# Sensor_LoRa_Moist.net
KiCad netlist of a schematic drawn in Altium Designer
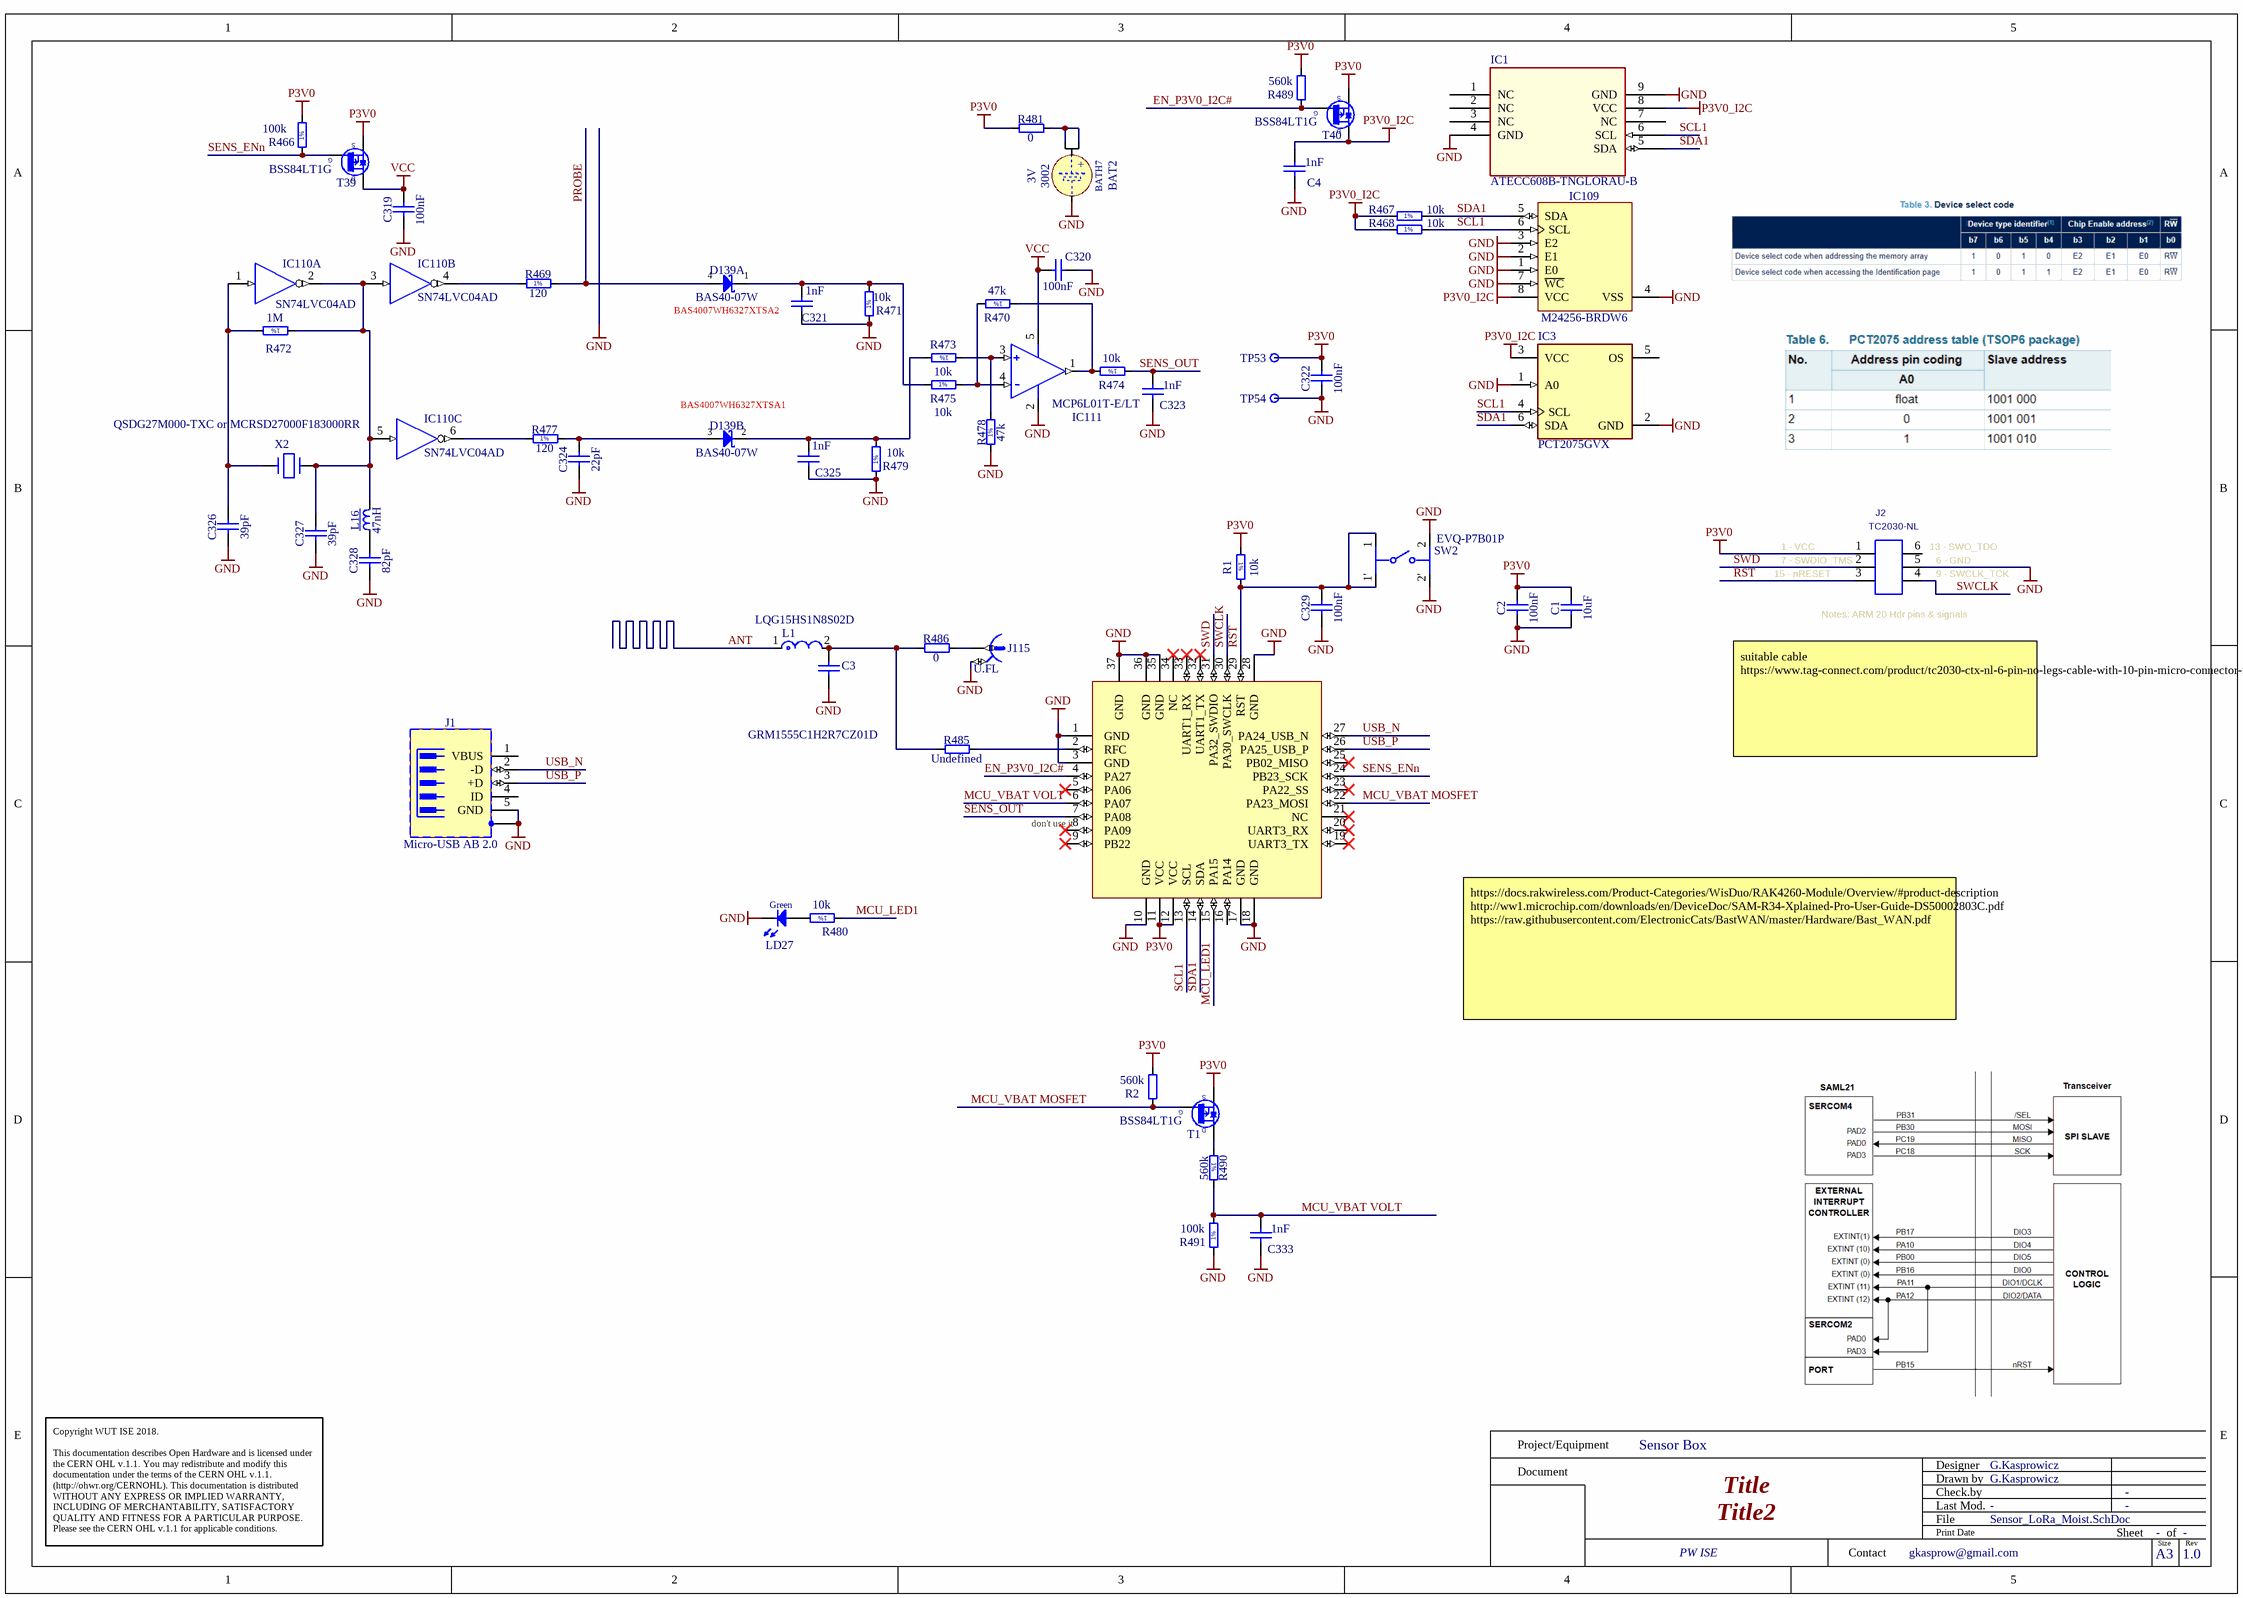
[diagram p0: Sensor_LoRa_Moist.SchDoc]

(export (version "E")
  (design (tool "Eeschema 10.0.6"))
  (components
    (comp (ref "BAT2")
      (value "3V")
      (footprint "BAT_VARTA_CR2032")
      (description "Battery for use only with Socket Holder")
      (fields
        (field (name "PART NUMBER") "BAT_VARTA_CR2032")
        (field (name "POWER") "230mAh")
        (field (name "AUTHOR") "CERN DEM JLC")
      )
      (libsource (lib "Eletro-mechanical") (part "Battery No Pin"))
    )
    (comp (ref "BATH7")
      (value "3002")
      (footprint "KEYSTONE 3002")
      (description "Battery Holder Keystone 3002")
      (fields
        (field (name "PART NUMBER") "BATH_KEYSTONE_3000")
        (field (name "MANUFACTURER") "KEYSTONE")
        (field (name "AUTHOR") "GK")
      )
      (libsource (lib "LIBRARY_SCH") (part "BATTERY_HOLD_CR2032_SMD"))
    )
    (comp (ref "C1")
      (value "10uF")
      (footprint "CAPC2012X135N")
      (description "Non-polarised capacitor")
      (fields
        (field (name "PART NUMBER") "CC0805_10UF_16V_10%_X5R")
        (field (name "VOLTAGE") "16V")
        (field (name "AUTHOR") "CERN DEM JLC")
      )
      (libsource (lib "Capacitors") (part "Capacitor - non polarized"))
    )
    (comp (ref "C2")
      (value "100nF")
      (footprint "CAPC1005X55N")
      (description "Non-polarised capacitor")
      (fields
        (field (name "PART NUMBER") "CC0402_100NF_16V_10%_X5R")
        (field (name "VOLTAGE") "16V")
        (field (name "AUTHOR") "CERN DEM JLC")
      )
      (libsource (lib "Capacitors") (part "Capacitor - non polarized"))
    )
    (comp (ref "C3")
      (value "GRM1555C1H2R7CZ01D")
      (footprint "CAPC1005X55X25ML05T10")
      (fields (field (name "MANUFACTURER") "Murata"))
      (libsource (lib "Altium Content Vault") (part "CAP"))
    )
    (comp (ref "C4")
      (value "1nF")
      (footprint "CAPC1005X55N")
      (description "Non-polarised capacitor")
      (fields
        (field (name "PART NUMBER") "CC0402_1NF_50V_10%_X7R")
        (field (name "VOLTAGE") "50V")
        (field (name "AUTHOR") "CERN DEM JLC")
      )
      (libsource (lib "Capacitors") (part "Capacitor - non polarized"))
    )
    (comp (ref "C319")
      (value "100nF")
      (footprint "CAPC1005X55N")
      (description "Non-polarised capacitor")
      (fields
        (field (name "PART NUMBER") "CC0402_100NF_16V_10%_X5R")
        (field (name "VOLTAGE") "16V")
        (field (name "AUTHOR") "CERN DEM JLC")
      )
      (libsource (lib "Capacitors") (part "Capacitor - non polarized"))
    )
    (comp (ref "C320")
      (value "100nF")
      (footprint "CAPC1005X55N")
      (description "Non-polarised capacitor")
      (fields
        (field (name "PART NUMBER") "CC0402_100NF_16V_10%_X5R")
        (field (name "VOLTAGE") "16V")
        (field (name "AUTHOR") "CERN DEM JLC")
      )
      (libsource (lib "Capacitors") (part "Capacitor - non polarized"))
    )
    (comp (ref "C321")
      (value "1nF")
      (footprint "CAPC1005X55N")
      (description "Non-polarised capacitor")
      (fields
        (field (name "PART NUMBER") "CC0402_1NF_50V_10%_X7R")
        (field (name "VOLTAGE") "50V")
        (field (name "AUTHOR") "CERN DEM JLC")
      )
      (libsource (lib "Capacitors") (part "Capacitor - non polarized"))
    )
    (comp (ref "C322")
      (value "100nF")
      (footprint "CAPC1005X55N")
      (description "Non-polarised capacitor")
      (fields
        (field (name "PART NUMBER") "CC0402_100NF_16V_10%_X5R")
        (field (name "VOLTAGE") "16V")
        (field (name "AUTHOR") "CERN DEM JLC")
      )
      (libsource (lib "Capacitors") (part "Capacitor - non polarized"))
    )
    (comp (ref "C323")
      (value "1nF")
      (footprint "CAPC1005X55N")
      (description "Non-polarised capacitor")
      (fields
        (field (name "PART NUMBER") "CC0402_1NF_50V_10%_X7R")
        (field (name "VOLTAGE") "50V")
        (field (name "AUTHOR") "CERN DEM JLC")
      )
      (libsource (lib "Capacitors") (part "Capacitor - non polarized"))
    )
    (comp (ref "C324")
      (value "22pF")
      (footprint "CAPC1005X55N")
      (description "Non-polarised capacitor")
      (fields
        (field (name "PART NUMBER") "CC0402_22PF_50V_5%_C0G")
        (field (name "VOLTAGE") "50V")
        (field (name "AUTHOR") "CERN DEM JLC")
      )
      (libsource (lib "Capacitors") (part "Capacitor - non polarized"))
    )
    (comp (ref "C325")
      (value "1nF")
      (footprint "CAPC1005X55N")
      (description "Non-polarised capacitor")
      (fields
        (field (name "PART NUMBER") "CC0402_1NF_50V_10%_X7R")
        (field (name "VOLTAGE") "50V")
        (field (name "AUTHOR") "CERN DEM JLC")
      )
      (libsource (lib "Capacitors") (part "Capacitor - non polarized"))
    )
    (comp (ref "C326")
      (value "39pF")
      (footprint "CAPC1608X87N")
      (description "Non-polarised capacitor")
      (fields
        (field (name "PART NUMBER") "CC0603_39PF_50V_5%_NP0")
        (field (name "VOLTAGE") "50V")
        (field (name "AUTHOR") "CERN DEM JLC")
      )
      (libsource (lib "Capacitors") (part "Capacitor - non polarized"))
    )
    (comp (ref "C327")
      (value "39pF")
      (footprint "CAPC1608X87N")
      (description "Non-polarised capacitor")
      (fields
        (field (name "PART NUMBER") "CC0603_39PF_50V_5%_NP0")
        (field (name "VOLTAGE") "50V")
        (field (name "AUTHOR") "CERN DEM JLC")
      )
      (libsource (lib "Capacitors") (part "Capacitor - non polarized"))
    )
    (comp (ref "C328")
      (value "82pF")
      (footprint "CAPC2012X90N")
      (description "Non-polarised capacitor")
      (fields
        (field (name "PART NUMBER") "CC0805_82PF_100V_1%_NP0_AVX_08051A820FAT2A")
        (field (name "VOLTAGE") "100V")
        (field (name "AUTHOR") "CERN DEM WB")
      )
      (libsource (lib "Capacitors") (part "Capacitor - non polarized"))
    )
    (comp (ref "C329")
      (value "100nF")
      (footprint "CAPC1005X55N")
      (description "Non-polarised capacitor")
      (fields
        (field (name "PART NUMBER") "CC0402_100NF_16V_10%_X5R")
        (field (name "VOLTAGE") "16V")
        (field (name "AUTHOR") "CERN DEM JLC")
      )
      (libsource (lib "Capacitors") (part "Capacitor - non polarized"))
    )
    (comp (ref "C333")
      (value "1nF")
      (footprint "CAPC1005X55N")
      (description "Non-polarised capacitor")
      (fields
        (field (name "PART NUMBER") "CC0402_1NF_50V_10%_X7R")
        (field (name "VOLTAGE") "50V")
        (field (name "AUTHOR") "CERN DEM JLC")
      )
      (libsource (lib "Capacitors") (part "Capacitor - non polarized"))
    )
    (comp (ref "D139")
      (value "BAS40-07W")
      (footprint "INFINEON-PG-SOT343-4")
      (description "Anti-Parallel Pair Schottky Diode")
      (fields
        (field (name "PART NUMBER") "BAS4007WH6327XTSA1")
        (field (name "VOLTAGE") "4V")
        (field (name "AUTHOR") "GK")
      )
      (libsource (lib "LIBRARY_SCH") (part "D_BAS40-07W"))
    )
    (comp (ref "IC1")
      (value "ATECC608B-TNGLORAU-B")
      (footprint "UDFN8_MUY/Q4B_MCH-L")
      (description "Pre-provisioned secure element for LoRaWAN")
      (fields (field (name "COPYRIGHT") "Copyright (C) 2018 Accelerated Designs. All rights reserved"))
      (libsource (lib "ICs_Analog_Interfaces") (part "CRYPTO_ATECC608B-TNGLORAU-B"))
    )
    (comp (ref "IC2")
      (value "RAK4260 - EU868")
      (footprint "RAK4260")
      (description "RAK4260 LoRaWAN module from RAKwireless.")
      (fields (field (name "MANUFACTURER") "RAK WIreless"))
      (libsource (lib "Modules") (part "RF_RAK4260"))
    )
    (comp (ref "IC3")
      (value "PCT2075GVX")
      (footprint "FP-SOT1353-1-MFG")
      (description "SENSOR DIGITAL -55C-125C 6TSOP")
      (fields
        (field (name "MANUFACTURER") "NXP Semiconductors")
        (field (name "OCTOPART") "https://octopart.com/pct2075gvx-nxp+semiconductors-50417606")
      )
      (libsource (lib "Altium Content Vault") (part "9e3f1a7ca589d645a6d0162f869e50e"))
    )
    (comp (ref "IC109")
      (value "M24256-BRDW6")
      (footprint "SOP65P640X120-8N")
      (description "256-Kbit Serial I²C Bus EEPROM")
      (fields
        (field (name "PART NUMBER") "M24256-BRDW6P")
        (field (name "MANUFACTURER") "ST MICROELECTRONICS")
        (field (name "AUTHOR") "CERN DEM MR")
      )
      (libsource (lib "LIBRARY_SCH") (part "MEM_M24256-BRDW6P"))
    )
    (comp (ref "IC110")
      (value "SN74LVC04AD")
      (footprint "SOIC127P600X175-14N")
      (description "Hex Inverter")
      (fields (field (name "MANUFACTURER") "TEXAS INSTRUMENTS") (field (name "AUTHOR") "CERN DEM JLC"))
      (libsource (lib "ICs And Semiconductors") (part "7404"))
    )
    (comp (ref "IC111")
      (value "MCP6L01T-E/LT")
      (footprint "SC70")
      (description "1 MHz, Low-Power Op Amp")
      (libsource (lib "LIBRARY_SCH") (part "OA_MCP6001_SC-70"))
    )
    (comp (ref "J1")
      (value "Micro-USB AB 2.0")
      (footprint "HIROSE_ZX62RD-AB-5P8")
      (description "5 Pin + 1 Shield USB Receptacle")
      (fields
        (field (name "PART NUMBER") "HIROSE_ZX62RD-AB-5P8")
        (field (name "MANUFACTURER") "HIROSE (HRS)")
        (field (name "AUTHOR") "CERN DEM JLC")
      )
      (libsource (lib "Connectors") (part "Connector USB 5 Pin + 1Shield"))
    )
    (comp (ref "J2")
      (value "TC2030-NL")
      (footprint "TC2030-IDC")
      (description "HDR, TC2030, 6 Pin, Footprint only")
      (libsource (lib "TagConnect-20Apr2013") (part "HDR 6 TC2030-NL"))
    )
    (comp (ref "J115")
      (value "U.FL")
      (footprint "HIROSE_U.FL-R-SMT-1(10)")
      (fields
        (field (name "PART NUMBER") "HIROSE_U.FL-R-SMT-1(10)")
        (field (name "MANUFACTURER") "HIROSE (HRS)")
        (field (name "MANUFACTURER PART NUMBER") "U.FL-R-SMT-1(10)")
        (field (name "AUTHOR") "CERN DEM JLC")
      )
      (libsource (lib "Connectors") (part "Coax_1Male_1Shield"))
    )
    (comp (ref "L1")
      (value "LQG15HS1N8S02D")
      (footprint "FP-LQG15HH_02-IPC_C")
      (description "Multilayer type RF Inductor 1.8nH ±0.3nH 0.08Ω 950mA 0402")
      (libsource (lib "Altium Content Vault") (part "4cc4b267dca4c8e51f7102f422741d8"))
    )
    (comp (ref "L16")
      (value "47nH")
      (footprint "IND_COILCRAFT_0805CS")
      (description "Inductor With Core")
      (fields
        (field (name "PART NUMBER") "IND_47NH_2%_COILCRAFT_0805CS")
        (field (name "POWER") "500mA")
        (field (name "AUTHOR") "CERN DEM JLC")
      )
      (libsource (lib "Inductors & Transformers") (part "Inductor With Magnetic core"))
    )
    (comp (ref "LD27")
      (value "Green")
      (footprint "LED_KINGBRIGHT_KPH-1608CGCK")
      (description "LED Green 1C 2A")
      (fields
        (field (name "PART NUMBER") "LED_KINGBRIGHT_KPH-1608CGCK")
        (field (name "MANUFACTURER") "KINGBRIGHT")
        (field (name "AUTHOR") "CERN DEM JLC")
      )
      (libsource (lib "ICs And Semiconductors") (part "LED Green 1C 2A"))
    )
    (comp (ref "R1")
      (value "10k")
      (footprint "RESC1005X40N")
      (description "Resistor - 1%")
      (fields
        (field (name "PART NUMBER") "R0402_10K_1%_0.0625W_100PPM")
        (field (name "POWER") "0.0625W")
        (field (name "AUTHOR") "CERN DEM JLC")
      )
      (libsource (lib "Resistors") (part "Resistor - 1%"))
    )
    (comp (ref "R2")
      (value "560k")
      (footprint "RESC1005X40N")
      (description "Resistor - 1%")
      (fields
        (field (name "PART NUMBER") "R0402_560K_1%_0.0625W_100PPM")
        (field (name "POWER") "0.0625W")
        (field (name "AUTHOR") "CERN DEM JLC")
      )
      (libsource (lib "Resistors") (part "Resistor - 1%"))
    )
    (comp (ref "R466")
      (value "100k")
      (footprint "RESC1005X40N")
      (description "Resistor - 1%")
      (fields
        (field (name "PART NUMBER") "R0402_100K_1%_0.0625W_100PPM")
        (field (name "POWER") "0.0625W")
        (field (name "AUTHOR") "CERN DEM JLC")
      )
      (libsource (lib "Resistors") (part "Resistor - 1%"))
    )
    (comp (ref "R467")
      (value "10k")
      (footprint "RESC1005X40N")
      (description "Resistor - 1%")
      (fields
        (field (name "PART NUMBER") "R0402_10K_1%_0.0625W_100PPM")
        (field (name "POWER") "0.0625W")
        (field (name "AUTHOR") "CERN DEM JLC")
      )
      (libsource (lib "Resistors") (part "Resistor - 1%"))
    )
    (comp (ref "R468")
      (value "10k")
      (footprint "RESC1005X40N")
      (description "Resistor - 1%")
      (fields
        (field (name "PART NUMBER") "R0402_10K_1%_0.0625W_100PPM")
        (field (name "POWER") "0.0625W")
        (field (name "AUTHOR") "CERN DEM JLC")
      )
      (libsource (lib "Resistors") (part "Resistor - 1%"))
    )
    (comp (ref "R469")
      (value "120")
      (footprint "RESC1005X40N")
      (description "Resistor - 1%")
      (fields
        (field (name "PART NUMBER") "R0402_120R_1%_0.0625W_100PPM")
        (field (name "POWER") "0.0625W")
        (field (name "AUTHOR") "CERN DEM JLC")
      )
      (libsource (lib "Resistors") (part "Resistor - 1%"))
    )
    (comp (ref "R470")
      (value "47k")
      (footprint "RESC1005X40N")
      (description "Resistor - 1%")
      (fields
        (field (name "PART NUMBER") "R0402_47K_1%_0.0625W_100PPM")
        (field (name "POWER") "0.0625W")
        (field (name "AUTHOR") "CERN DEM JLC")
      )
      (libsource (lib "Resistors") (part "Resistor - 1%"))
    )
    (comp (ref "R471")
      (value "10k")
      (footprint "RESC1005X40N")
      (description "Resistor - 1%")
      (fields
        (field (name "PART NUMBER") "R0402_10K_1%_0.0625W_100PPM")
        (field (name "POWER") "0.0625W")
        (field (name "AUTHOR") "CERN DEM JLC")
      )
      (libsource (lib "Resistors") (part "Resistor - 1%"))
    )
    (comp (ref "R472")
      (value "1M")
      (footprint "RESC1005X40N")
      (description "Resistor - 1%")
      (fields
        (field (name "PART NUMBER") "R0402_1M_1%_0.0625W_100PPM")
        (field (name "POWER") "0.0625W")
        (field (name "AUTHOR") "CERN DEM JLC")
      )
      (libsource (lib "Resistors") (part "Resistor - 1%"))
    )
    (comp (ref "R473")
      (value "10k")
      (footprint "RESC1005X40N")
      (description "Resistor - 1%")
      (fields
        (field (name "PART NUMBER") "R0402_10K_1%_0.0625W_100PPM")
        (field (name "POWER") "0.0625W")
        (field (name "AUTHOR") "CERN DEM JLC")
      )
      (libsource (lib "Resistors") (part "Resistor - 1%"))
    )
    (comp (ref "R474")
      (value "10k")
      (footprint "RESC1005X40N")
      (description "Resistor - 1%")
      (fields
        (field (name "PART NUMBER") "R0402_10K_1%_0.0625W_100PPM")
        (field (name "POWER") "0.0625W")
        (field (name "AUTHOR") "CERN DEM JLC")
      )
      (libsource (lib "Resistors") (part "Resistor - 1%"))
    )
    (comp (ref "R475")
      (value "10k")
      (footprint "RESC1005X40N")
      (description "Resistor - 1%")
      (fields
        (field (name "PART NUMBER") "R0402_10K_1%_0.0625W_100PPM")
        (field (name "POWER") "0.0625W")
        (field (name "AUTHOR") "CERN DEM JLC")
      )
      (libsource (lib "Resistors") (part "Resistor - 1%"))
    )
    (comp (ref "R477")
      (value "120")
      (footprint "RESC1005X40N")
      (description "Resistor - 1%")
      (fields
        (field (name "PART NUMBER") "R0402_120R_1%_0.0625W_100PPM")
        (field (name "POWER") "0.0625W")
        (field (name "AUTHOR") "CERN DEM JLC")
      )
      (libsource (lib "Resistors") (part "Resistor - 1%"))
    )
    (comp (ref "R478")
      (value "47k")
      (footprint "RESC1005X40N")
      (description "Resistor - 1%")
      (fields
        (field (name "PART NUMBER") "R0402_47K_1%_0.0625W_100PPM")
        (field (name "POWER") "0.0625W")
        (field (name "AUTHOR") "CERN DEM JLC")
      )
      (libsource (lib "Resistors") (part "Resistor - 1%"))
    )
    (comp (ref "R479")
      (value "10k")
      (footprint "RESC1005X40N")
      (description "Resistor - 1%")
      (fields
        (field (name "PART NUMBER") "R0402_10K_1%_0.0625W_100PPM")
        (field (name "POWER") "0.0625W")
        (field (name "AUTHOR") "CERN DEM JLC")
      )
      (libsource (lib "Resistors") (part "Resistor - 1%"))
    )
    (comp (ref "R480")
      (value "10k")
      (footprint "RESC1005X40N")
      (description "Resistor - 1%")
      (fields
        (field (name "PART NUMBER") "R0402_10K_1%_0.0625W_100PPM")
        (field (name "POWER") "0.0625W")
        (field (name "AUTHOR") "CERN DEM JLC")
      )
      (libsource (lib "Resistors") (part "Resistor - 1%"))
    )
    (comp (ref "R481")
      (value "0")
      (footprint "RESC1608X55N")
      (description "Resistor")
      (fields
        (field (name "PART NUMBER") "R0603_0R_JUMPER")
        (field (name "MANUFACTURER") "GENERIC")
        (field (name "AUTHOR") "CERN DEM JLC")
      )
      (libsource (lib "Resistors") (part "Resistor"))
    )
    (comp (ref "R485")
      (value "Undefined")
      (footprint "RESC1608X55N")
      (description "Resistor")
      (fields (field (name "PART NUMBER") "R0603_NO-VALUE") (field (name "AUTHOR") "CERN DEM JLC"))
      (libsource (lib "Resistors") (part "Resistor"))
    )
    (comp (ref "R486")
      (value "0")
      (footprint "RESC1608X55N")
      (description "Resistor")
      (fields
        (field (name "PART NUMBER") "R0603_0R_JUMPER")
        (field (name "MANUFACTURER") "GENERIC")
        (field (name "AUTHOR") "CERN DEM JLC")
      )
      (libsource (lib "Resistors") (part "Resistor"))
    )
    (comp (ref "R489")
      (value "560k")
      (footprint "RESC1005X40N")
      (description "Resistor - 1%")
      (fields
        (field (name "PART NUMBER") "R0402_560K_1%_0.0625W_100PPM")
        (field (name "POWER") "0.0625W")
        (field (name "AUTHOR") "CERN DEM JLC")
      )
      (libsource (lib "Resistors") (part "Resistor - 1%"))
    )
    (comp (ref "R490")
      (value "560k")
      (footprint "RESC1005X40N")
      (description "Resistor - 1%")
      (fields
        (field (name "PART NUMBER") "R0402_560K_1%_0.0625W_100PPM")
        (field (name "POWER") "0.0625W")
        (field (name "AUTHOR") "CERN DEM JLC")
      )
      (libsource (lib "Resistors") (part "Resistor - 1%"))
    )
    (comp (ref "R491")
      (value "100k")
      (footprint "RESC1005X40N")
      (description "Resistor - 1%")
      (fields
        (field (name "PART NUMBER") "R0402_100K_1%_0.0625W_100PPM")
        (field (name "POWER") "0.0625W")
        (field (name "AUTHOR") "CERN DEM JLC")
      )
      (libsource (lib "Resistors") (part "Resistor - 1%"))
    )
    (comp (ref "SW2")
      (value "EVQ-P7B01P")
      (footprint "FP-EVQ-P7B01P-MFG")
      (description "SWITCH TACTILE SPST-NO 0.05A 12V")
      (libsource (lib "Altium Content Vault") (part "210e32ac5400ec01d635f9bada53656"))
    )
    (comp (ref "T1")
      (value "BSS84LT1G")
      (footprint "SOT95P240X110-3N")
      (description "P-CHANNEL MOSFET WITH DIODE")
      (fields (field (name "MANUFACTURER") "ON SEMICONDUCTOR") (field (name "AUTHOR") "CERN DEM JLC"))
      (libsource (lib "ICs And Semiconductors") (part "P-MOSFET-D 1G 2S 3D"))
    )
    (comp (ref "T39")
      (value "BSS84LT1G")
      (footprint "SOT95P240X110-3N")
      (description "P-CHANNEL MOSFET WITH DIODE")
      (fields (field (name "MANUFACTURER") "ON SEMICONDUCTOR") (field (name "AUTHOR") "CERN DEM JLC"))
      (libsource (lib "ICs And Semiconductors") (part "P-MOSFET-D 1G 2S 3D"))
    )
    (comp (ref "T40")
      (value "BSS84LT1G")
      (footprint "SOT95P240X110-3N")
      (description "P-CHANNEL MOSFET WITH DIODE")
      (fields (field (name "MANUFACTURER") "ON SEMICONDUCTOR") (field (name "AUTHOR") "CERN DEM JLC"))
      (libsource (lib "ICs And Semiconductors") (part "P-MOSFET-D 1G 2S 3D"))
    )
    (comp (ref "TP53")
      (value "Test Point")
      (footprint "TPS127")
      (fields (field (name "PART NUMBER") "SMD_PAD_1.27X1.27MM") (field (name "AUTHOR") "CERN DEM JLC"))
      (libsource (lib "Eletro-mechanical") (part "Test Point"))
    )
    (comp (ref "TP54")
      (value "Test Point")
      (footprint "TPS127")
      (fields (field (name "PART NUMBER") "SMD_PAD_1.27X1.27MM") (field (name "AUTHOR") "CERN DEM JLC"))
      (libsource (lib "Eletro-mechanical") (part "Test Point"))
    )
    (comp (ref "X2")
      (value "QSDG27M000-TXC or MCRSD27000F183000RR")
      (footprint "HC-49SM")
      (description "Crystal oscillator")
      (libsource (lib "LIBRARY_SCH") (part "X_CRYSTAL_HC49_SMT_27M"))
    )
  )
  (nets
    (net (code "1") (name "/ANT") (class "Default")
      (node (ref "L1") (pin "1") (pinfunction "1_1") (pintype "passive"))
    )
    (net (code "2") (name "/EN_P3V0_I2C#") (class "Default")
      (node (ref "IC2") (pin "4") (pinfunction "PA27_4") (pintype "bidirectional"))
      (node (ref "R489") (pin "1") (pinfunction "1_1") (pintype "passive"))
      (node (ref "T40") (pin "1") (pinfunction "G_1") (pintype "passive"))
    )
    (net (code "3") (name "/MCU_LED1") (class "Default")
      (node (ref "IC2") (pin "15") (pinfunction "PA15_15") (pintype "bidirectional"))
      (node (ref "R480") (pin "1") (pinfunction "1_1") (pintype "passive"))
    )
    (net (code "4") (name "/MCU_VBAT MOSFET") (class "Default")
      (node (ref "IC2") (pin "22") (pinfunction "PA23_MOSI_22") (pintype "bidirectional"))
      (node (ref "R2") (pin "1") (pinfunction "1_1") (pintype "passive"))
      (node (ref "T1") (pin "1") (pinfunction "G_1") (pintype "passive"))
    )
    (net (code "5") (name "/MCU_VBAT VOLT") (class "Default")
      (node (ref "C333") (pin "2") (pinfunction "2_2") (pintype "passive"))
      (node (ref "IC2") (pin "6") (pinfunction "PA07_6") (pintype "bidirectional"))
      (node (ref "R490") (pin "2") (pinfunction "2_2") (pintype "passive"))
      (node (ref "R491") (pin "2") (pinfunction "2_2") (pintype "passive"))
    )
    (net (code "6") (name "/PROBE") (class "Default")
      (node (ref "D139") (pin "4") (pinfunction "A_4") (pintype "passive"))
      (node (ref "R469") (pin "2") (pinfunction "2_2") (pintype "passive"))
    )
    (net (code "7") (name "/RST") (class "Default")
      (node (ref "C329") (pin "2") (pinfunction "2_2") (pintype "passive"))
      (node (ref "IC2") (pin "29") (pinfunction "RST_29") (pintype "bidirectional"))
      (node (ref "J2") (pin "3") (pinfunction "3_3") (pintype "passive"))
      (node (ref "R1") (pin "2") (pinfunction "2_2") (pintype "passive"))
      (node (ref "SW2") (pin "1") (pinfunction "1_1") (pintype "passive"))
      (node (ref "SW2") (pin "1'") (pinfunction "1'_1'") (pintype "passive"))
    )
    (net (code "8") (name "/SCL1") (class "Default")
      (node (ref "IC1") (pin "6") (pinfunction "SCL_6") (pintype "input"))
      (node (ref "IC109") (pin "6") (pinfunction "SCL_6") (pintype "input"))
      (node (ref "IC2") (pin "13") (pinfunction "SCL_13") (pintype "bidirectional"))
      (node (ref "IC3") (pin "4") (pinfunction "SCL_4") (pintype "input"))
      (node (ref "R468") (pin "2") (pinfunction "2_2") (pintype "passive"))
    )
    (net (code "9") (name "/SDA1") (class "Default")
      (node (ref "IC1") (pin "5") (pinfunction "SDA_5") (pintype "bidirectional"))
      (node (ref "IC109") (pin "5") (pinfunction "SDA_5") (pintype "bidirectional"))
      (node (ref "IC2") (pin "14") (pinfunction "SDA_14") (pintype "bidirectional"))
      (node (ref "IC3") (pin "6") (pinfunction "SDA_6") (pintype "bidirectional"))
      (node (ref "R467") (pin "2") (pinfunction "2_2") (pintype "passive"))
    )
    (net (code "10") (name "/SENS_ENn") (class "Default")
      (node (ref "IC2") (pin "24") (pinfunction "PB23_SCK_24") (pintype "bidirectional"))
      (node (ref "R466") (pin "1") (pinfunction "1_1") (pintype "passive"))
      (node (ref "T39") (pin "1") (pinfunction "G_1") (pintype "passive"))
    )
    (net (code "11") (name "/SENS_OUT") (class "Default")
      (node (ref "C323") (pin "2") (pinfunction "2_2") (pintype "passive"))
      (node (ref "IC2") (pin "7") (pinfunction "PA08_7") (pintype "bidirectional"))
      (node (ref "R474") (pin "1") (pinfunction "1_1") (pintype "passive"))
    )
    (net (code "12") (name "/SWCLK") (class "Default")
      (node (ref "IC2") (pin "30") (pinfunction "PA30_SWCLK_30") (pintype "bidirectional"))
      (node (ref "J2") (pin "4") (pinfunction "4_4") (pintype "passive"))
    )
    (net (code "13") (name "/SWD") (class "Default")
      (node (ref "IC2") (pin "31") (pinfunction "PA32_SWDIO_31") (pintype "bidirectional"))
      (node (ref "J2") (pin "2") (pinfunction "2_2") (pintype "passive"))
    )
    (net (code "14") (name "/USB_N") (class "Default")
      (node (ref "IC2") (pin "27") (pinfunction "PA24_USB_N_27") (pintype "bidirectional"))
      (node (ref "J1") (pin "2") (pinfunction "-D_2") (pintype "bidirectional"))
    )
    (net (code "15") (name "/USB_P") (class "Default")
      (node (ref "IC2") (pin "26") (pinfunction "PA25_USB_P_26") (pintype "bidirectional"))
      (node (ref "J1") (pin "3") (pinfunction "+D_3") (pintype "bidirectional"))
    )
    (net (code "16") (name "GND") (class "Default")
      (node (ref "BATH7") (pin "2") (pinfunction "MINUS_2") (pintype "power_in"))
      (node (ref "C1") (pin "1") (pinfunction "1_1") (pintype "passive"))
      (node (ref "C2") (pin "1") (pinfunction "1_1") (pintype "passive"))
      (node (ref "C3") (pin "1") (pinfunction "1_1") (pintype "passive"))
      (node (ref "C319") (pin "1") (pinfunction "1_1") (pintype "passive"))
      (node (ref "C320") (pin "2") (pinfunction "2_2") (pintype "passive"))
      (node (ref "C321") (pin "1") (pinfunction "1_1") (pintype "passive"))
      (node (ref "C322") (pin "1") (pinfunction "1_1") (pintype "passive"))
      (node (ref "C323") (pin "1") (pinfunction "1_1") (pintype "passive"))
      (node (ref "C324") (pin "1") (pinfunction "1_1") (pintype "passive"))
      (node (ref "C325") (pin "1") (pinfunction "1_1") (pintype "passive"))
      (node (ref "C326") (pin "1") (pinfunction "1_1") (pintype "passive"))
      (node (ref "C327") (pin "1") (pinfunction "1_1") (pintype "passive"))
      (node (ref "C328") (pin "1") (pinfunction "1_1") (pintype "passive"))
      (node (ref "C329") (pin "1") (pinfunction "1_1") (pintype "passive"))
      (node (ref "C333") (pin "1") (pinfunction "1_1") (pintype "passive"))
      (node (ref "C4") (pin "1") (pinfunction "1_1") (pintype "passive"))
      (node (ref "IC1") (pin "4") (pinfunction "GND_4") (pintype "passive"))
      (node (ref "IC1") (pin "9") (pinfunction "GND_9") (pintype "passive"))
      (node (ref "IC109") (pin "1") (pinfunction "E0_1") (pintype "input"))
      (node (ref "IC109") (pin "2") (pinfunction "E1_2") (pintype "input"))
      (node (ref "IC109") (pin "3") (pinfunction "E2_3") (pintype "input"))
      (node (ref "IC109") (pin "4") (pinfunction "VSS_4") (pintype "power_in"))
      (node (ref "IC109") (pin "7") (pinfunction "~{WC}_7") (pintype "input"))
      (node (ref "IC110") (pin "7") (pinfunction "GND_7") (pintype "power_in"))
      (node (ref "IC111") (pin "2") (pinfunction "V-_2") (pintype "power_in"))
      (node (ref "IC2") (pin "1") (pinfunction "GND_1") (pintype "power_in"))
      (node (ref "IC2") (pin "10") (pinfunction "GND_10") (pintype "power_in"))
      (node (ref "IC2") (pin "17") (pinfunction "GND_17") (pintype "power_in"))
      (node (ref "IC2") (pin "18") (pinfunction "GND_18") (pintype "power_in"))
      (node (ref "IC2") (pin "28") (pinfunction "GND_28") (pintype "power_in"))
      (node (ref "IC2") (pin "3") (pinfunction "GND_3") (pintype "power_in"))
      (node (ref "IC2") (pin "35") (pinfunction "GND_35") (pintype "power_in"))
      (node (ref "IC2") (pin "36") (pinfunction "GND_36") (pintype "power_in"))
      (node (ref "IC2") (pin "37") (pinfunction "GND_37") (pintype "power_in"))
      (node (ref "IC3") (pin "1") (pinfunction "A0_1") (pintype "input"))
      (node (ref "IC3") (pin "2") (pinfunction "GND_2") (pintype "power_in"))
      (node (ref "J1") (pin "5") (pinfunction "GND_5") (pintype "power_in"))
      (node (ref "J1") (pin "6") (pinfunction "SH_6") (pintype "power_in"))
      (node (ref "J115") (pin "2") (pinfunction "2_2") (pintype "bidirectional"))
      (node (ref "J2") (pin "5") (pinfunction "5_5") (pintype "passive"))
      (node (ref "LD27") (pin "1") (pinfunction "C_1") (pintype "passive"))
      (node (ref "R471") (pin "1") (pinfunction "1_1") (pintype "passive"))
      (node (ref "R478") (pin "1") (pinfunction "1_1") (pintype "passive"))
      (node (ref "R479") (pin "1") (pinfunction "1_1") (pintype "passive"))
      (node (ref "R491") (pin "1") (pinfunction "1_1") (pintype "passive"))
      (node (ref "SW2") (pin "2") (pinfunction "2_2") (pintype "passive"))
      (node (ref "SW2") (pin "2'") (pinfunction "2'_2'") (pintype "passive"))
      (node (ref "TP54") (pin "1") (pinfunction "1_1") (pintype "bidirectional"))
    )
    (net (code "17") (name "Net-(BATH7-PLUS-Pad1a)") (class "Default")
      (node (ref "BATH7") (pin "1a") (pinfunction "PLUS_1a") (pintype "power_in"))
      (node (ref "BATH7") (pin "1b") (pinfunction "PLUS_1b") (pintype "power_in"))
      (node (ref "R481") (pin "2") (pinfunction "2_2") (pintype "passive"))
    )
    (net (code "18") (name "Net-(C3-Pad2)") (class "Default")
      (node (ref "C3") (pin "2") (pinfunction "2_2") (pintype "passive"))
      (node (ref "L1") (pin "2") (pinfunction "2_2") (pintype "passive"))
      (node (ref "R485") (pin "2") (pinfunction "2_2") (pintype "passive"))
      (node (ref "R486") (pin "2") (pinfunction "2_2") (pintype "passive"))
    )
    (net (code "19") (name "Net-(C328-Pad2)") (class "Default")
      (node (ref "C328") (pin "2") (pinfunction "2_2") (pintype "passive"))
      (node (ref "L16") (pin "1") (pinfunction "1_1") (pintype "passive"))
    )
    (net (code "20") (name "Net-(D139A-C)") (class "Default")
      (node (ref "C321") (pin "2") (pinfunction "2_2") (pintype "passive"))
      (node (ref "D139") (pin "1") (pinfunction "C_1") (pintype "passive"))
      (node (ref "R471") (pin "2") (pinfunction "2_2") (pintype "passive"))
      (node (ref "R475") (pin "1") (pinfunction "1_1") (pintype "passive"))
    )
    (net (code "21") (name "Net-(D139B-A)") (class "Default")
      (node (ref "C325") (pin "2") (pinfunction "2_2") (pintype "passive"))
      (node (ref "D139") (pin "2") (pinfunction "A_2") (pintype "passive"))
      (node (ref "R473") (pin "2") (pinfunction "2_2") (pintype "passive"))
      (node (ref "R479") (pin "2") (pinfunction "2_2") (pintype "passive"))
    )
    (net (code "22") (name "Net-(D139B-C)") (class "Default")
      (node (ref "C324") (pin "2") (pinfunction "2_2") (pintype "passive"))
      (node (ref "D139") (pin "3") (pinfunction "C_3") (pintype "passive"))
      (node (ref "R477") (pin "2") (pinfunction "2_2") (pintype "passive"))
    )
    (net (code "23") (name "Net-(IC2-RFC)") (class "Default")
      (node (ref "IC2") (pin "2") (pinfunction "RFC_2") (pintype "bidirectional"))
      (node (ref "R485") (pin "1") (pinfunction "1_1") (pintype "passive"))
    )
    (net (code "24") (name "Net-(IC110A-A)") (class "Default")
      (node (ref "C326") (pin "2") (pinfunction "2_2") (pintype "passive"))
      (node (ref "IC110") (pin "1") (pinfunction "A_1") (pintype "input"))
      (node (ref "R472") (pin "2") (pinfunction "2_2") (pintype "passive"))
      (node (ref "X2") (pin "1") (pinfunction "1_1") (pintype "passive"))
    )
    (net (code "25") (name "Net-(IC110A-~{O})") (class "Default")
      (node (ref "C327") (pin "2") (pinfunction "2_2") (pintype "passive"))
      (node (ref "IC110") (pin "2") (pinfunction "~{O}_2") (pintype "output"))
      (node (ref "IC110") (pin "3") (pinfunction "A_3") (pintype "input"))
      (node (ref "IC110") (pin "5") (pinfunction "A_5") (pintype "input"))
      (node (ref "L16") (pin "2") (pinfunction "2_2") (pintype "passive"))
      (node (ref "R472") (pin "1") (pinfunction "1_1") (pintype "passive"))
      (node (ref "X2") (pin "2") (pinfunction "2_2") (pintype "passive"))
    )
    (net (code "26") (name "Net-(IC110B-~{O})") (class "Default")
      (node (ref "IC110") (pin "4") (pinfunction "~{O}_4") (pintype "output"))
      (node (ref "R469") (pin "1") (pinfunction "1_1") (pintype "passive"))
    )
    (net (code "27") (name "Net-(IC110C-~{O})") (class "Default")
      (node (ref "IC110") (pin "6") (pinfunction "~{O}_6") (pintype "output"))
      (node (ref "R477") (pin "1") (pinfunction "1_1") (pintype "passive"))
    )
    (net (code "28") (name "Net-(IC111-IN+)") (class "Default")
      (node (ref "IC111") (pin "3") (pinfunction "IN+_3") (pintype "input"))
      (node (ref "R473") (pin "1") (pinfunction "1_1") (pintype "passive"))
      (node (ref "R478") (pin "2") (pinfunction "2_2") (pintype "passive"))
    )
    (net (code "29") (name "Net-(IC111-OUT)") (class "Default")
      (node (ref "IC111") (pin "1") (pinfunction "OUT_1") (pintype "output"))
      (node (ref "R470") (pin "1") (pinfunction "1_1") (pintype "passive"))
      (node (ref "R474") (pin "2") (pinfunction "2_2") (pintype "passive"))
    )
    (net (code "30") (name "Net-(IC111-in-)") (class "Default")
      (node (ref "IC111") (pin "4") (pinfunction "in-_4") (pintype "input"))
      (node (ref "R470") (pin "2") (pinfunction "2_2") (pintype "passive"))
      (node (ref "R475") (pin "2") (pinfunction "2_2") (pintype "passive"))
    )
    (net (code "31") (name "Net-(J115-Pad1)") (class "Default")
      (node (ref "J115") (pin "1") (pinfunction "1_1") (pintype "bidirectional"))
      (node (ref "R486") (pin "1") (pinfunction "1_1") (pintype "passive"))
    )
    (net (code "32") (name "Net-(LD27-A)") (class "Default")
      (node (ref "LD27") (pin "2") (pinfunction "A_2") (pintype "passive"))
      (node (ref "R480") (pin "2") (pinfunction "2_2") (pintype "passive"))
    )
    (net (code "33") (name "Net-(T1-D)") (class "Default")
      (node (ref "R490") (pin "1") (pinfunction "1_1") (pintype "passive"))
      (node (ref "T1") (pin "3") (pinfunction "D_3") (pintype "passive"))
    )
    (net (code "34") (name "P3V0") (class "Default")
      (node (ref "C1") (pin "2") (pinfunction "2_2") (pintype "passive"))
      (node (ref "C2") (pin "2") (pinfunction "2_2") (pintype "passive"))
      (node (ref "C322") (pin "2") (pinfunction "2_2") (pintype "passive"))
      (node (ref "IC2") (pin "11") (pinfunction "VCC_11") (pintype "power_in"))
      (node (ref "IC2") (pin "12") (pinfunction "VCC_12") (pintype "power_in"))
      (node (ref "J2") (pin "1") (pinfunction "1_1") (pintype "passive"))
      (node (ref "R1") (pin "1") (pinfunction "1_1") (pintype "passive"))
      (node (ref "R2") (pin "2") (pinfunction "2_2") (pintype "passive"))
      (node (ref "R466") (pin "2") (pinfunction "2_2") (pintype "passive"))
      (node (ref "R481") (pin "1") (pinfunction "1_1") (pintype "passive"))
      (node (ref "R489") (pin "2") (pinfunction "2_2") (pintype "passive"))
      (node (ref "T1") (pin "2") (pinfunction "S_2") (pintype "passive"))
      (node (ref "T39") (pin "2") (pinfunction "S_2") (pintype "passive"))
      (node (ref "T40") (pin "2") (pinfunction "S_2") (pintype "passive"))
      (node (ref "TP53") (pin "1") (pinfunction "1_1") (pintype "bidirectional"))
    )
    (net (code "35") (name "P3V0_I2C") (class "Default")
      (node (ref "C4") (pin "2") (pinfunction "2_2") (pintype "passive"))
      (node (ref "IC1") (pin "8") (pinfunction "VCC_8") (pintype "power_in"))
      (node (ref "IC109") (pin "8") (pinfunction "VCC_8") (pintype "power_in"))
      (node (ref "IC3") (pin "3") (pinfunction "VCC_3") (pintype "power_in"))
      (node (ref "R467") (pin "1") (pinfunction "1_1") (pintype "passive"))
      (node (ref "R468") (pin "1") (pinfunction "1_1") (pintype "passive"))
      (node (ref "T40") (pin "3") (pinfunction "D_3") (pintype "passive"))
    )
    (net (code "36") (name "VCC") (class "Default")
      (node (ref "C319") (pin "2") (pinfunction "2_2") (pintype "passive"))
      (node (ref "C320") (pin "1") (pinfunction "1_1") (pintype "passive"))
      (node (ref "IC110") (pin "14") (pinfunction "VCC_14") (pintype "power_in"))
      (node (ref "IC111") (pin "5") (pinfunction "V+_5") (pintype "power_in"))
      (node (ref "T39") (pin "3") (pinfunction "D_3") (pintype "passive"))
    )
    (net (code "37") (name "unconnected-(IC1-NC-Pad1)") (class "Default")
      (node (ref "IC1") (pin "1") (pinfunction "NC_1") (pintype "passive"))
    )
    (net (code "38") (name "unconnected-(IC1-NC-Pad2)") (class "Default")
      (node (ref "IC1") (pin "2") (pinfunction "NC_2") (pintype "passive"))
    )
    (net (code "39") (name "unconnected-(IC1-NC-Pad3)") (class "Default")
      (node (ref "IC1") (pin "3") (pinfunction "NC_3") (pintype "passive"))
    )
    (net (code "40") (name "unconnected-(IC1-NC-Pad7)") (class "Default")
      (node (ref "IC1") (pin "7") (pinfunction "NC_7") (pintype "passive"))
    )
    (net (code "41") (name "unconnected-(IC2-NC-Pad21)") (class "Default")
      (node (ref "IC2") (pin "21") (pinfunction "NC_21") (pintype "passive+no_connect"))
    )
    (net (code "42") (name "unconnected-(IC2-NC-Pad34)") (class "Default")
      (node (ref "IC2") (pin "34") (pinfunction "NC_34") (pintype "passive+no_connect"))
    )
    (net (code "43") (name "unconnected-(IC2-PA06-Pad5)") (class "Default")
      (node (ref "IC2") (pin "5") (pinfunction "PA06_5") (pintype "bidirectional+no_connect"))
    )
    (net (code "44") (name "unconnected-(IC2-PA09-Pad8)") (class "Default")
      (node (ref "IC2") (pin "8") (pinfunction "PA09_8") (pintype "bidirectional+no_connect"))
    )
    (net (code "45") (name "unconnected-(IC2-PA14-Pad16)") (class "Default")
      (node (ref "IC2") (pin "16") (pinfunction "PA14_16") (pintype "bidirectional"))
    )
    (net (code "46") (name "unconnected-(IC2-PA22_SS-Pad23)") (class "Default")
      (node (ref "IC2") (pin "23") (pinfunction "PA22_SS_23") (pintype "bidirectional+no_connect"))
    )
    (net (code "47") (name "unconnected-(IC2-PB02_MISO-Pad25)") (class "Default")
      (node (ref "IC2") (pin "25") (pinfunction "PB02_MISO_25") (pintype "bidirectional+no_connect"))
    )
    (net (code "48") (name "unconnected-(IC2-PB22-Pad9)") (class "Default")
      (node (ref "IC2") (pin "9") (pinfunction "PB22_9") (pintype "bidirectional+no_connect"))
    )
    (net (code "49") (name "unconnected-(IC2-UART1_RX-Pad33)") (class "Default")
      (node (ref "IC2") (pin "33") (pinfunction "UART1_RX_33") (pintype "bidirectional+no_connect"))
    )
    (net (code "50") (name "unconnected-(IC2-UART1_TX-Pad32)") (class "Default")
      (node (ref "IC2") (pin "32") (pinfunction "UART1_TX_32") (pintype "bidirectional+no_connect"))
    )
    (net (code "51") (name "unconnected-(IC2-UART3_RX-Pad20)") (class "Default")
      (node (ref "IC2") (pin "20") (pinfunction "UART3_RX_20") (pintype "bidirectional+no_connect"))
    )
    (net (code "52") (name "unconnected-(IC2-UART3_TX-Pad19)") (class "Default")
      (node (ref "IC2") (pin "19") (pinfunction "UART3_TX_19") (pintype "bidirectional+no_connect"))
    )
    (net (code "53") (name "unconnected-(IC3-OS-Pad5)") (class "Default")
      (node (ref "IC3") (pin "5") (pinfunction "OS_5") (pintype "open_collector"))
    )
    (net (code "54") (name "unconnected-(J1-ID-Pad4)") (class "Default")
      (node (ref "J1") (pin "4") (pinfunction "ID_4") (pintype "passive"))
    )
    (net (code "55") (name "unconnected-(J1-VBUS-Pad1)") (class "Default")
      (node (ref "J1") (pin "1") (pinfunction "VBUS_1") (pintype "power_in"))
    )
    (net (code "56") (name "unconnected-(J2-Pad6)") (class "Default")
      (node (ref "J2") (pin "6") (pinfunction "6_6") (pintype "passive"))
    )
  )
)
